# exp_xml.net
KiCad netlist of a schematic drawn in EAGLE
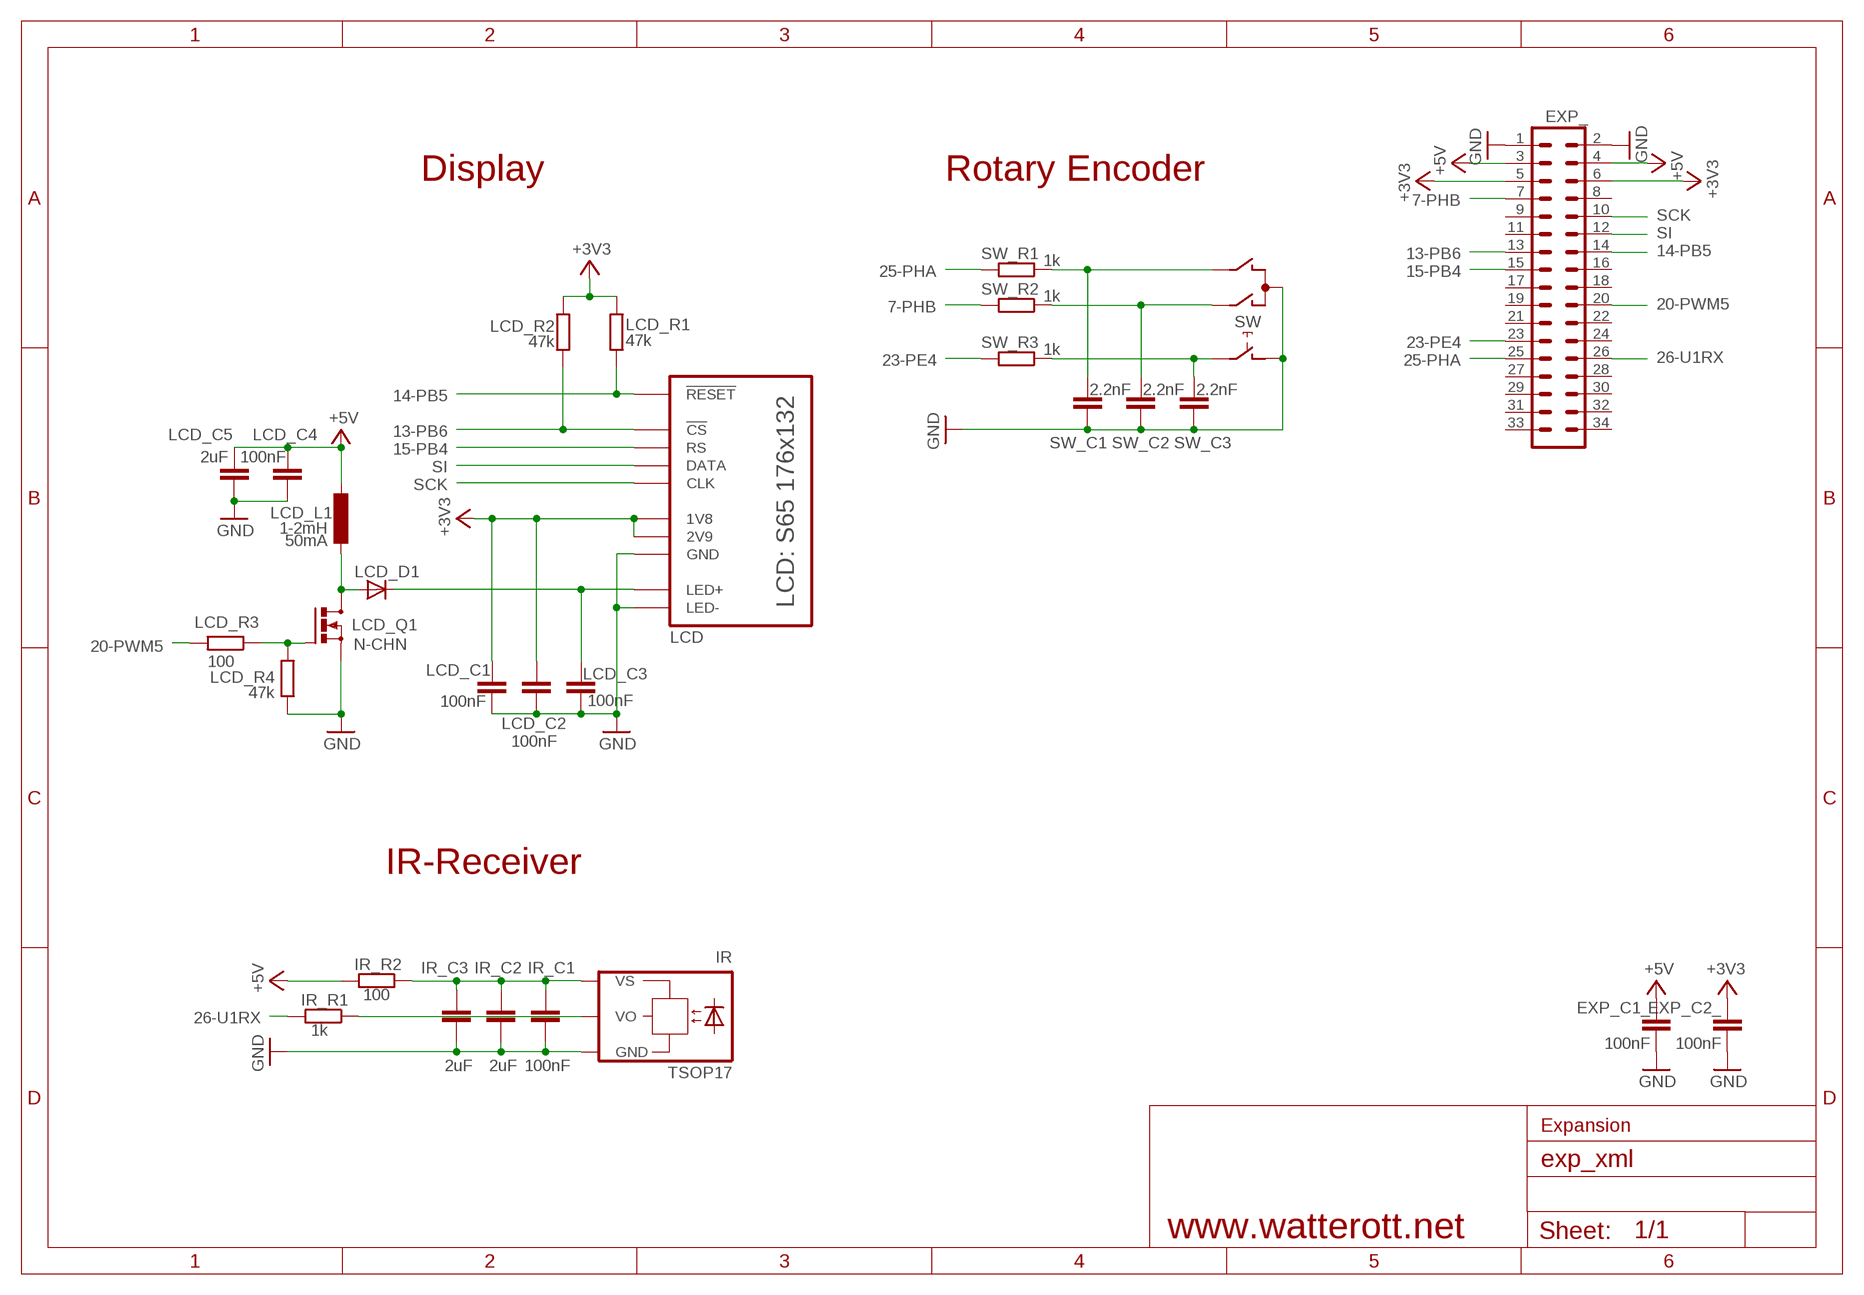
[diagram p0: schematic, sheet 1]

(export (version "E")
  (design (tool "Eeschema 10.0.6"))
  (components
    (comp (ref "EXP_")
      (value "MA17-2")
      (footprint "eagle-import:MA17-2")
      (libsource (lib "eagle-import") (part "MA17-2"))
    )
    (comp (ref "EXP_C1_")
      (value "100nF")
      (footprint "eagle-import:C0603")
      (libsource (lib "eagle-import") (part "C-EUC0603"))
    )
    (comp (ref "EXP_C2_")
      (value "100nF")
      (footprint "eagle-import:C0603")
      (libsource (lib "eagle-import") (part "C-EUC0603"))
    )
    (comp (ref "IR")
      (value "TSOP17")
      (footprint "eagle-import:TSOP17")
      (libsource (lib "eagle-import") (part "TSOP17"))
    )
    (comp (ref "IR_C1")
      (value "100nF")
      (footprint "eagle-import:C0603")
      (libsource (lib "eagle-import") (part "C-EUC0603"))
    )
    (comp (ref "IR_C2")
      (value "2uF")
      (footprint "eagle-import:C0603K")
      (libsource (lib "eagle-import") (part "C-EUC0603K"))
    )
    (comp (ref "IR_C3")
      (value "2uF")
      (footprint "eagle-import:C0603K")
      (libsource (lib "eagle-import") (part "C-EUC0603K"))
    )
    (comp (ref "IR_R1")
      (value "1k")
      (footprint "eagle-import:R0603")
      (libsource (lib "eagle-import") (part "R-EU_R0603"))
    )
    (comp (ref "IR_R2")
      (value "100")
      (footprint "eagle-import:R0603")
      (libsource (lib "eagle-import") (part "R-EU_R0603"))
    )
    (comp (ref "LCD")
      (value "S65")
      (footprint "eagle-import:S65")
      (libsource (lib "eagle-import") (part "S65"))
    )
    (comp (ref "LCD_C1")
      (value "100nF")
      (footprint "eagle-import:C0603")
      (libsource (lib "eagle-import") (part "C-EUC0603"))
    )
    (comp (ref "LCD_C2")
      (value "100nF")
      (footprint "eagle-import:C0603")
      (libsource (lib "eagle-import") (part "C-EUC0603"))
    )
    (comp (ref "LCD_C3")
      (value "100nF")
      (footprint "eagle-import:C0603")
      (libsource (lib "eagle-import") (part "C-EUC0603"))
    )
    (comp (ref "LCD_C4")
      (value "100nF")
      (footprint "eagle-import:C0603")
      (libsource (lib "eagle-import") (part "C-EUC0603"))
    )
    (comp (ref "LCD_C5")
      (value "2uF")
      (footprint "eagle-import:C0603K")
      (libsource (lib "eagle-import") (part "C-EUC0603K"))
    )
    (comp (ref "LCD_D1")
      (value "DIODE-DO214AA")
      (footprint "eagle-import:DO214AA")
      (libsource (lib "eagle-import") (part "DIODE-DO214AA"))
    )
    (comp (ref "LCD_L1")
      (value "1-2mH")
      (footprint "eagle-import:L4532M")
      (libsource (lib "eagle-import") (part "L-EUL4532C"))
    )
    (comp (ref "LCD_Q1")
      (value "N-CHN")
      (footprint "eagle-import:MICRO3")
      (libsource (lib "eagle-import") (part "IRLML2502"))
    )
    (comp (ref "LCD_R1")
      (value "47k")
      (footprint "eagle-import:R0603")
      (libsource (lib "eagle-import") (part "R-EU_R0603"))
    )
    (comp (ref "LCD_R2")
      (value "47k")
      (footprint "eagle-import:R0603")
      (libsource (lib "eagle-import") (part "R-EU_R0603"))
    )
    (comp (ref "LCD_R3")
      (value "100")
      (footprint "eagle-import:R0603")
      (libsource (lib "eagle-import") (part "R-EU_R0603"))
    )
    (comp (ref "LCD_R4")
      (value "47k")
      (footprint "eagle-import:R0603")
      (libsource (lib "eagle-import") (part "R-EU_R0603"))
    )
    (comp (ref "SW")
      (value "EC12E_SW")
      (footprint "eagle-import:ALPS_EC12E_SW")
      (libsource (lib "eagle-import") (part "EC12E_SW"))
    )
    (comp (ref "SW_C1")
      (value "2.2nF")
      (footprint "eagle-import:C0603")
      (libsource (lib "eagle-import") (part "C-EUC0603"))
    )
    (comp (ref "SW_C2")
      (value "2.2nF")
      (footprint "eagle-import:C0603")
      (libsource (lib "eagle-import") (part "C-EUC0603"))
    )
    (comp (ref "SW_C3")
      (value "2.2nF")
      (footprint "eagle-import:C0603")
      (libsource (lib "eagle-import") (part "C-EUC0603"))
    )
    (comp (ref "SW_R1")
      (value "1k")
      (footprint "eagle-import:R0603")
      (libsource (lib "eagle-import") (part "R-EU_R0603"))
    )
    (comp (ref "SW_R2")
      (value "1k")
      (footprint "eagle-import:R0603")
      (libsource (lib "eagle-import") (part "R-EU_R0603"))
    )
    (comp (ref "SW_R3")
      (value "1k")
      (footprint "eagle-import:R0603")
      (libsource (lib "eagle-import") (part "R-EU_R0603"))
    )
  )
  (nets
    (net (code "1") (name "+3V3") (class "Default")
      (node (ref "EXP_") (pin "5") (pinfunction "5_5") (pintype "passive"))
      (node (ref "EXP_") (pin "6") (pinfunction "6_6") (pintype "passive"))
      (node (ref "EXP_C2_") (pin "1") (pinfunction "1_1") (pintype "passive"))
      (node (ref "LCD") (pin "1V8") (pinfunction "1V8_1V8") (pintype "power_in"))
      (node (ref "LCD") (pin "2V9") (pinfunction "2V9_2V9") (pintype "power_in"))
      (node (ref "LCD_C1") (pin "1") (pinfunction "1_1") (pintype "passive"))
      (node (ref "LCD_C2") (pin "1") (pinfunction "1_1") (pintype "passive"))
      (node (ref "LCD_R1") (pin "1") (pinfunction "1_1") (pintype "passive"))
      (node (ref "LCD_R2") (pin "1") (pinfunction "1_1") (pintype "passive"))
    )
    (net (code "2") (name "+5V") (class "Default")
      (node (ref "EXP_") (pin "3") (pinfunction "3_3") (pintype "passive"))
      (node (ref "EXP_") (pin "4") (pinfunction "4_4") (pintype "passive"))
      (node (ref "EXP_C1_") (pin "1") (pinfunction "1_1") (pintype "passive"))
      (node (ref "IR_R2") (pin "2") (pinfunction "2_2") (pintype "passive"))
      (node (ref "LCD_C4") (pin "1") (pinfunction "1_1") (pintype "passive"))
      (node (ref "LCD_C5") (pin "1") (pinfunction "1_1") (pintype "passive"))
      (node (ref "LCD_L1") (pin "2") (pinfunction "2_2") (pintype "passive"))
    )
    (net (code "3") (name "/7-PHB") (class "Default")
      (node (ref "EXP_") (pin "7") (pinfunction "7_7") (pintype "passive"))
      (node (ref "SW_R2") (pin "2") (pinfunction "2_2") (pintype "passive"))
    )
    (net (code "4") (name "/13-PB6") (class "Default")
      (node (ref "EXP_") (pin "13") (pinfunction "13_13") (pintype "passive"))
      (node (ref "LCD") (pin "CS") (pinfunction "~{CS}_CS") (pintype "bidirectional"))
      (node (ref "LCD_R2") (pin "2") (pinfunction "2_2") (pintype "passive"))
    )
    (net (code "5") (name "/14-PB5") (class "Default")
      (node (ref "EXP_") (pin "14") (pinfunction "14_14") (pintype "passive"))
      (node (ref "LCD") (pin "RESET") (pinfunction "~{RESET}_RESET") (pintype "bidirectional"))
      (node (ref "LCD_R1") (pin "2") (pinfunction "2_2") (pintype "passive"))
    )
    (net (code "6") (name "/15-PB4") (class "Default")
      (node (ref "EXP_") (pin "15") (pinfunction "15_15") (pintype "passive"))
      (node (ref "LCD") (pin "RS") (pinfunction "RS_RS") (pintype "bidirectional"))
    )
    (net (code "7") (name "/20-PWM5") (class "Default")
      (node (ref "EXP_") (pin "20") (pinfunction "20_20") (pintype "passive"))
      (node (ref "LCD_R3") (pin "2") (pinfunction "2_2") (pintype "passive"))
    )
    (net (code "8") (name "/23-PE4") (class "Default")
      (node (ref "EXP_") (pin "23") (pinfunction "23_23") (pintype "passive"))
      (node (ref "SW_R3") (pin "2") (pinfunction "2_2") (pintype "passive"))
    )
    (net (code "9") (name "/25-PHA") (class "Default")
      (node (ref "EXP_") (pin "25") (pinfunction "25_25") (pintype "passive"))
      (node (ref "SW_R1") (pin "2") (pinfunction "2_2") (pintype "passive"))
    )
    (net (code "10") (name "/26-U1RX") (class "Default")
      (node (ref "EXP_") (pin "26") (pinfunction "26_26") (pintype "passive"))
      (node (ref "IR_R1") (pin "2") (pinfunction "2_2") (pintype "passive"))
    )
    (net (code "11") (name "/SCK") (class "Default")
      (node (ref "EXP_") (pin "10") (pinfunction "10_10") (pintype "passive"))
      (node (ref "LCD") (pin "CLK") (pinfunction "CLK_CLK") (pintype "bidirectional"))
    )
    (net (code "12") (name "/SI") (class "Default")
      (node (ref "EXP_") (pin "12") (pinfunction "12_12") (pintype "passive"))
      (node (ref "LCD") (pin "DATA") (pinfunction "DATA_DATA") (pintype "bidirectional"))
    )
    (net (code "13") (name "GND") (class "Default")
      (node (ref "EXP_") (pin "1") (pinfunction "1_1") (pintype "passive"))
      (node (ref "EXP_") (pin "2") (pinfunction "2_2") (pintype "passive"))
      (node (ref "EXP_C1_") (pin "2") (pinfunction "2_2") (pintype "passive"))
      (node (ref "EXP_C2_") (pin "2") (pinfunction "2_2") (pintype "passive"))
      (node (ref "IR") (pin "GND") (pinfunction "GND_GND") (pintype "power_in"))
      (node (ref "IR_C1") (pin "2") (pinfunction "2_2") (pintype "passive"))
      (node (ref "IR_C2") (pin "2") (pinfunction "2_2") (pintype "passive"))
      (node (ref "IR_C3") (pin "2") (pinfunction "2_2") (pintype "passive"))
      (node (ref "LCD") (pin "GND") (pinfunction "GND_GND") (pintype "power_in"))
      (node (ref "LCD") (pin "LED-") (pinfunction "LED-_LED-") (pintype "power_in"))
      (node (ref "LCD_C1") (pin "2") (pinfunction "2_2") (pintype "passive"))
      (node (ref "LCD_C2") (pin "2") (pinfunction "2_2") (pintype "passive"))
      (node (ref "LCD_C3") (pin "2") (pinfunction "2_2") (pintype "passive"))
      (node (ref "LCD_C4") (pin "2") (pinfunction "2_2") (pintype "passive"))
      (node (ref "LCD_C5") (pin "2") (pinfunction "2_2") (pintype "passive"))
      (node (ref "LCD_Q1") (pin "2") (pinfunction "S_2") (pintype "passive"))
      (node (ref "LCD_R4") (pin "1") (pinfunction "1_1") (pintype "passive"))
      (node (ref "SW") (pin "C") (pinfunction "C_C") (pintype "passive"))
      (node (ref "SW") (pin "D") (pinfunction "1_D") (pintype "passive"))
      (node (ref "SW_C1") (pin "1") (pinfunction "1_1") (pintype "passive"))
      (node (ref "SW_C2") (pin "1") (pinfunction "1_1") (pintype "passive"))
      (node (ref "SW_C3") (pin "1") (pinfunction "1_1") (pintype "passive"))
    )
    (net (code "14") (name "Net-(IR-PadVO)") (class "Default")
      (node (ref "IR") (pin "VO") (pinfunction "VO_VO") (pintype "open_collector"))
      (node (ref "IR_R1") (pin "1") (pinfunction "1_1") (pintype "passive"))
    )
    (net (code "15") (name "Net-(IR-PadVS)") (class "Default")
      (node (ref "IR") (pin "VS") (pinfunction "VS_VS") (pintype "power_in"))
      (node (ref "IR_C1") (pin "1") (pinfunction "1_1") (pintype "passive"))
      (node (ref "IR_C2") (pin "1") (pinfunction "1_1") (pintype "passive"))
      (node (ref "IR_C3") (pin "1") (pinfunction "1_1") (pintype "passive"))
      (node (ref "IR_R2") (pin "1") (pinfunction "1_1") (pintype "passive"))
    )
    (net (code "16") (name "Net-(LCD-PadLED+)") (class "Default")
      (node (ref "LCD") (pin "LED+") (pinfunction "LED+_LED+") (pintype "power_in"))
      (node (ref "LCD_C3") (pin "1") (pinfunction "1_1") (pintype "passive"))
      (node (ref "LCD_D1") (pin "C") (pinfunction "C_C") (pintype "passive"))
    )
    (net (code "17") (name "Net-(LCD_Q1-D)") (class "Default")
      (node (ref "LCD_D1") (pin "A") (pinfunction "A_A") (pintype "passive"))
      (node (ref "LCD_L1") (pin "1") (pinfunction "1_1") (pintype "passive"))
      (node (ref "LCD_Q1") (pin "3") (pinfunction "D_3") (pintype "passive"))
    )
    (net (code "18") (name "Net-(LCD_Q1-G)") (class "Default")
      (node (ref "LCD_Q1") (pin "1") (pinfunction "G_1") (pintype "passive"))
      (node (ref "LCD_R3") (pin "1") (pinfunction "1_1") (pintype "passive"))
      (node (ref "LCD_R4") (pin "2") (pinfunction "2_2") (pintype "passive"))
    )
    (net (code "19") (name "Net-(SW-PadA)") (class "Default")
      (node (ref "SW") (pin "A") (pinfunction "A_A") (pintype "passive"))
      (node (ref "SW_C2") (pin "2") (pinfunction "2_2") (pintype "passive"))
      (node (ref "SW_R2") (pin "1") (pinfunction "1_1") (pintype "passive"))
    )
    (net (code "20") (name "Net-(SW-PadB)") (class "Default")
      (node (ref "SW") (pin "B") (pinfunction "B_B") (pintype "passive"))
      (node (ref "SW_C1") (pin "2") (pinfunction "2_2") (pintype "passive"))
      (node (ref "SW_R1") (pin "1") (pinfunction "1_1") (pintype "passive"))
    )
    (net (code "21") (name "Net-(SWB-2)") (class "Default")
      (node (ref "SW") (pin "E") (pinfunction "2_E") (pintype "passive"))
      (node (ref "SW_C3") (pin "2") (pinfunction "2_2") (pintype "passive"))
      (node (ref "SW_R3") (pin "1") (pinfunction "1_1") (pintype "passive"))
    )
    (net (code "22") (name "unconnected-(EXP_-Pad8)") (class "Default")
      (node (ref "EXP_") (pin "8") (pinfunction "8_8") (pintype "passive"))
    )
    (net (code "23") (name "unconnected-(EXP_-Pad9)") (class "Default")
      (node (ref "EXP_") (pin "9") (pinfunction "9_9") (pintype "passive"))
    )
    (net (code "24") (name "unconnected-(EXP_-Pad11)") (class "Default")
      (node (ref "EXP_") (pin "11") (pinfunction "11_11") (pintype "passive"))
    )
    (net (code "25") (name "unconnected-(EXP_-Pad16)") (class "Default")
      (node (ref "EXP_") (pin "16") (pinfunction "16_16") (pintype "passive"))
    )
    (net (code "26") (name "unconnected-(EXP_-Pad17)") (class "Default")
      (node (ref "EXP_") (pin "17") (pinfunction "17_17") (pintype "passive"))
    )
    (net (code "27") (name "unconnected-(EXP_-Pad18)") (class "Default")
      (node (ref "EXP_") (pin "18") (pinfunction "18_18") (pintype "passive"))
    )
    (net (code "28") (name "unconnected-(EXP_-Pad19)") (class "Default")
      (node (ref "EXP_") (pin "19") (pinfunction "19_19") (pintype "passive"))
    )
    (net (code "29") (name "unconnected-(EXP_-Pad21)") (class "Default")
      (node (ref "EXP_") (pin "21") (pinfunction "21_21") (pintype "passive"))
    )
    (net (code "30") (name "unconnected-(EXP_-Pad22)") (class "Default")
      (node (ref "EXP_") (pin "22") (pinfunction "22_22") (pintype "passive"))
    )
    (net (code "31") (name "unconnected-(EXP_-Pad24)") (class "Default")
      (node (ref "EXP_") (pin "24") (pinfunction "24_24") (pintype "passive"))
    )
    (net (code "32") (name "unconnected-(EXP_-Pad27)") (class "Default")
      (node (ref "EXP_") (pin "27") (pinfunction "27_27") (pintype "passive"))
    )
    (net (code "33") (name "unconnected-(EXP_-Pad28)") (class "Default")
      (node (ref "EXP_") (pin "28") (pinfunction "28_28") (pintype "passive"))
    )
    (net (code "34") (name "unconnected-(EXP_-Pad29)") (class "Default")
      (node (ref "EXP_") (pin "29") (pinfunction "29_29") (pintype "passive"))
    )
    (net (code "35") (name "unconnected-(EXP_-Pad30)") (class "Default")
      (node (ref "EXP_") (pin "30") (pinfunction "30_30") (pintype "passive"))
    )
    (net (code "36") (name "unconnected-(EXP_-Pad31)") (class "Default")
      (node (ref "EXP_") (pin "31") (pinfunction "31_31") (pintype "passive"))
    )
    (net (code "37") (name "unconnected-(EXP_-Pad32)") (class "Default")
      (node (ref "EXP_") (pin "32") (pinfunction "32_32") (pintype "passive"))
    )
    (net (code "38") (name "unconnected-(EXP_-Pad33)") (class "Default")
      (node (ref "EXP_") (pin "33") (pinfunction "33_33") (pintype "passive"))
    )
    (net (code "39") (name "unconnected-(EXP_-Pad34)") (class "Default")
      (node (ref "EXP_") (pin "34") (pinfunction "34_34") (pintype "passive"))
    )
  )
)
